# main_v2.net
KiCad netlist of a schematic drawn in EAGLE
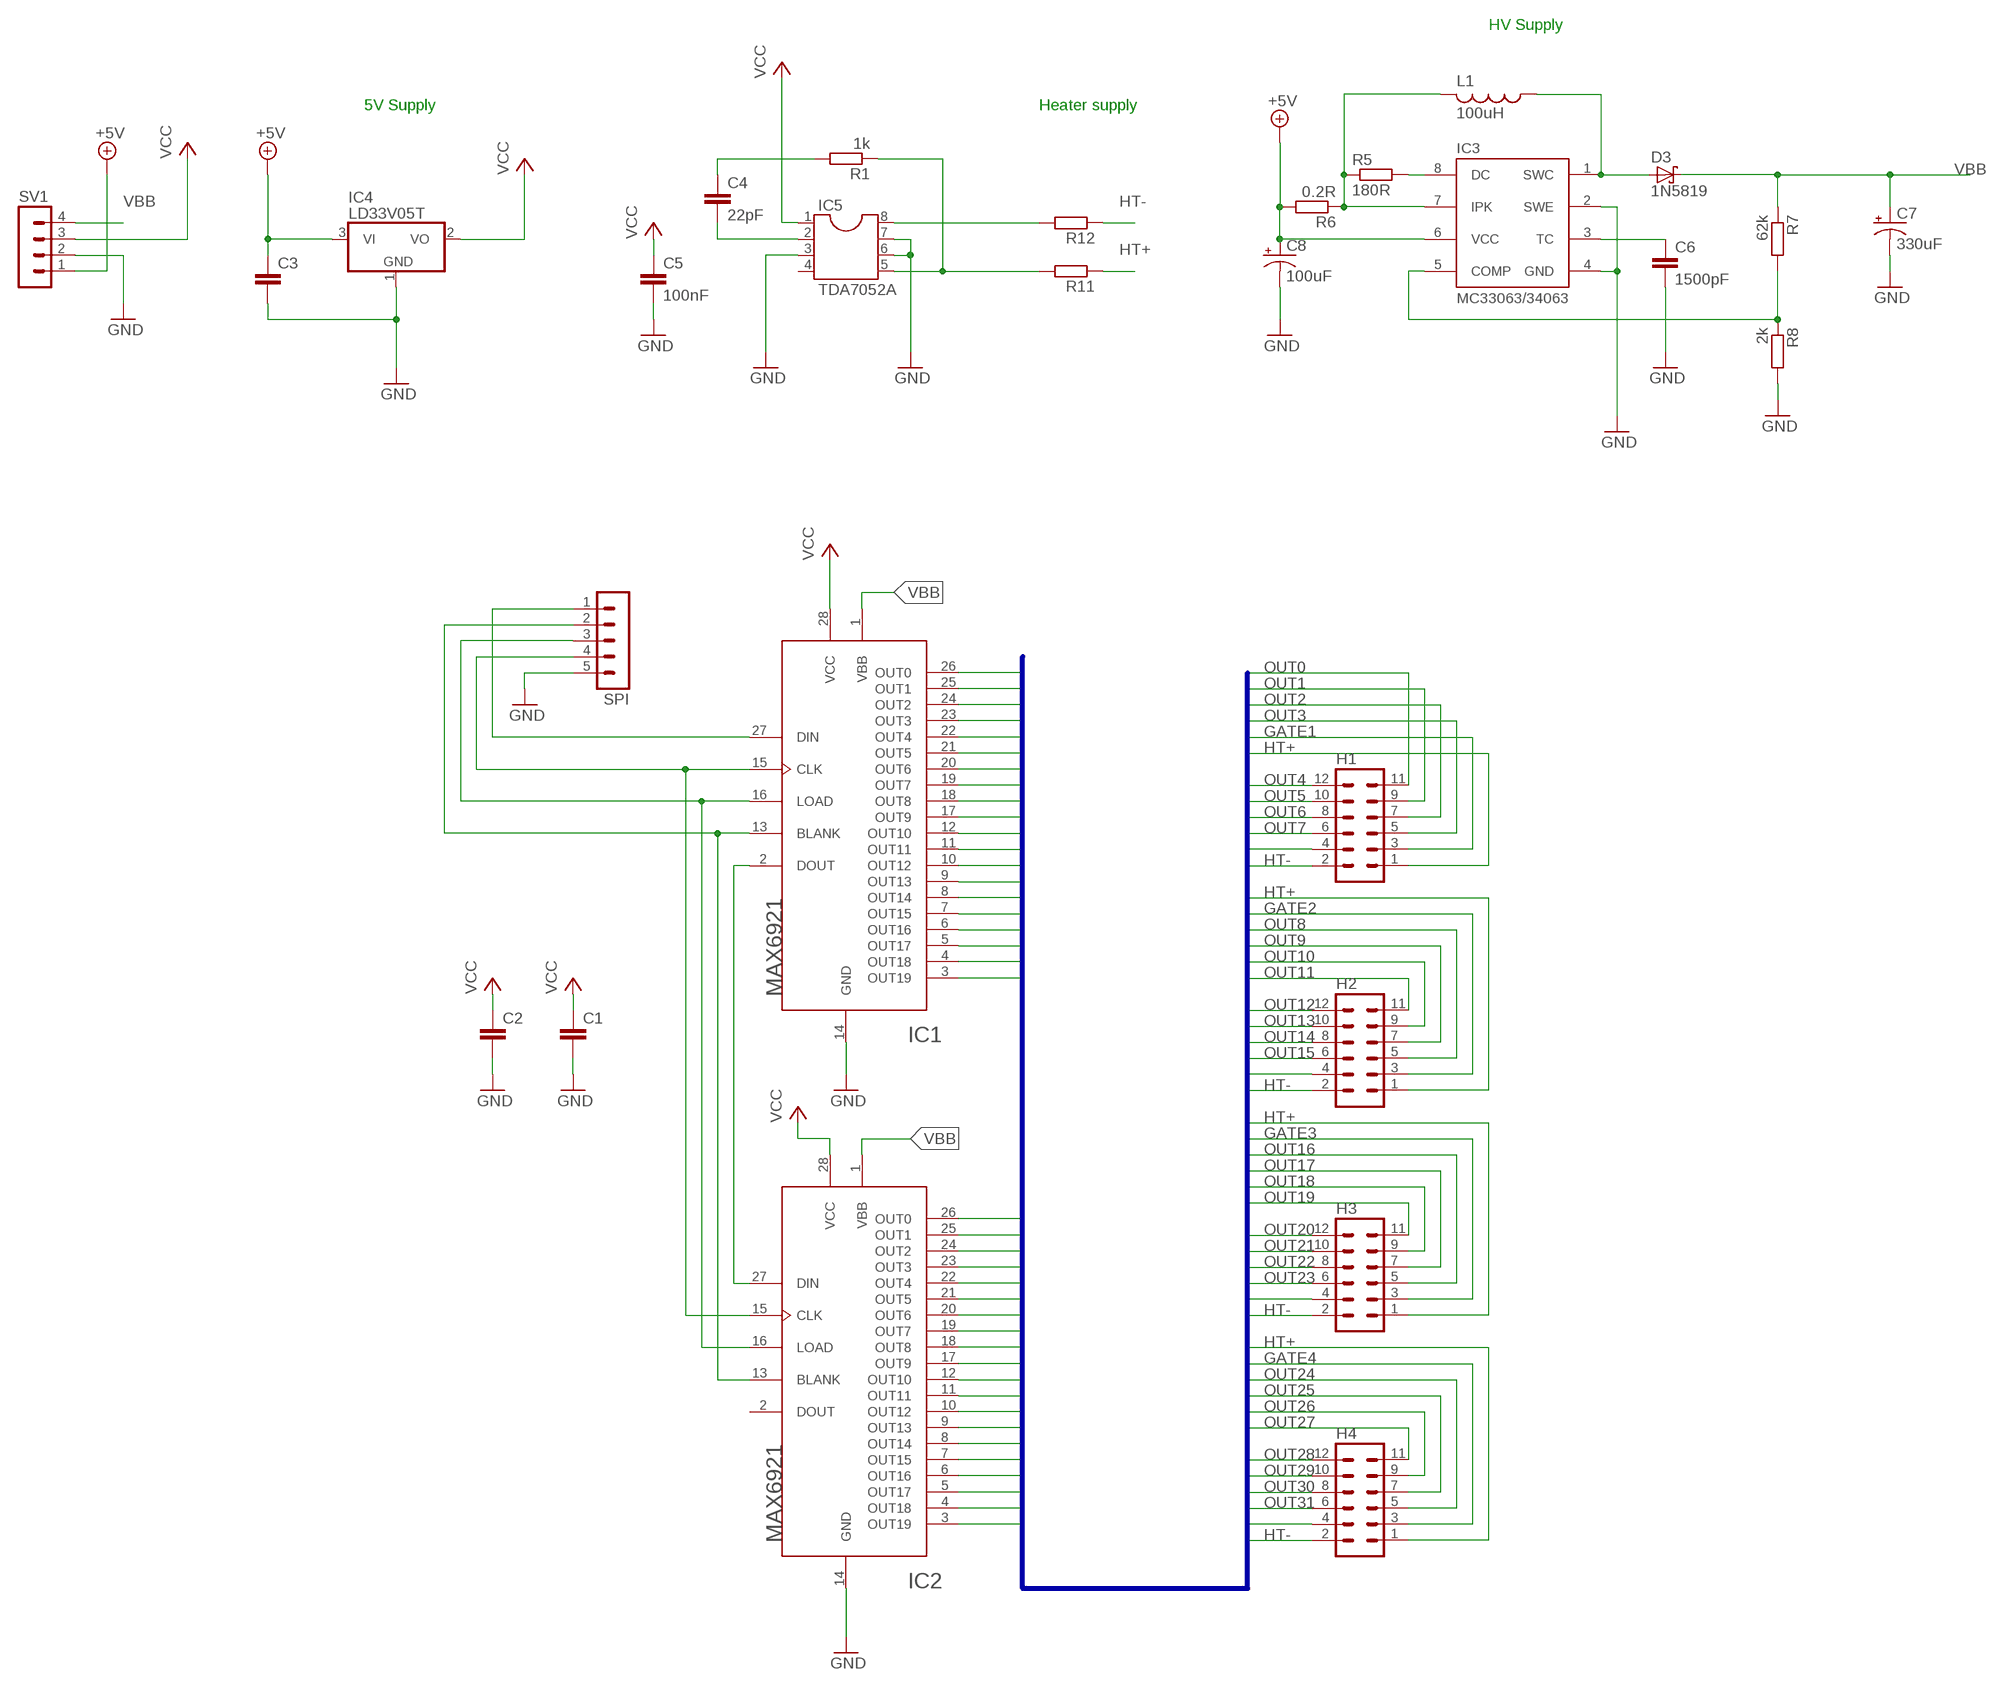
[diagram p0: schematic, sheet 1]

(export (version "E")
  (design (tool "Eeschema 10.0.6"))
  (components
    (comp (ref "C1")
      (value "C-EU025-025X050")
      (footprint "eagle-import:C025-025X050")
      (libsource (lib "eagle-import") (part "C-EU025-025X050"))
    )
    (comp (ref "C2")
      (value "C-EU025-025X050")
      (footprint "eagle-import:C025-025X050")
      (libsource (lib "eagle-import") (part "C-EU025-025X050"))
    )
    (comp (ref "C3")
      (value "C-EU025-025X050")
      (footprint "eagle-import:C025-025X050")
      (libsource (lib "eagle-import") (part "C-EU025-025X050"))
    )
    (comp (ref "C4")
      (value "22pF")
      (footprint "eagle-import:C025-025X050")
      (libsource (lib "eagle-import") (part "C-EU025-025X050"))
    )
    (comp (ref "C5")
      (value "100nF")
      (footprint "eagle-import:C025-025X050")
      (libsource (lib "eagle-import") (part "C-EU025-025X050"))
    )
    (comp (ref "C6")
      (value "1500pF")
      (footprint "eagle-import:C025-025X050")
      (libsource (lib "eagle-import") (part "C-EU025-025X050"))
    )
    (comp (ref "C7")
      (value "330uF")
      (footprint "eagle-import:E3,5-8")
      (libsource (lib "eagle-import") (part "CPOL-USE3.5-8"))
    )
    (comp (ref "C8")
      (value "100uF")
      (footprint "eagle-import:E2,5-5")
      (libsource (lib "eagle-import") (part "CPOL-USE2.5-5"))
    )
    (comp (ref "D3")
      (value "1N5819")
      (footprint "eagle-import:DO35-7")
      (libsource (lib "eagle-import") (part "SCHOTTKY-DIODEDO35-7"))
    )
    (comp (ref "H1")
      (value "MA06-2")
      (footprint "eagle-import:MA06-2")
      (libsource (lib "eagle-import") (part "MA06-2"))
    )
    (comp (ref "H2")
      (value "MA06-2")
      (footprint "eagle-import:MA06-2")
      (libsource (lib "eagle-import") (part "MA06-2"))
    )
    (comp (ref "H3")
      (value "MA06-2")
      (footprint "eagle-import:MA06-2")
      (libsource (lib "eagle-import") (part "MA06-2"))
    )
    (comp (ref "H4")
      (value "MA06-2")
      (footprint "eagle-import:MA06-2")
      (libsource (lib "eagle-import") (part "MA06-2"))
    )
    (comp (ref "IC1")
      (value "MAX6921")
      (footprint "eagle-import:PLCC-S28")
      (libsource (lib "eagle-import") (part "MAX6921"))
    )
    (comp (ref "IC2")
      (value "MAX6921")
      (footprint "eagle-import:PLCC-S28")
      (libsource (lib "eagle-import") (part "MAX6921"))
    )
    (comp (ref "IC3")
      (value "MC33063")
      (footprint "eagle-import:DIL08")
      (libsource (lib "eagle-import") (part "MC33063/MC34063P"))
    )
    (comp (ref "IC4")
      (value "LD33V05T")
      (footprint "eagle-import:TO220H")
      (libsource (lib "eagle-import") (part "LD33VT05"))
    )
    (comp (ref "IC5")
      (value "TDA7052A")
      (footprint "eagle-import:DIL08")
      (libsource (lib "eagle-import") (part "DIL8"))
    )
    (comp (ref "L1")
      (value "100uH")
      (footprint "eagle-import:6000-XXXX-RC")
      (libsource (lib "eagle-import") (part "L-US6000-XXX-RC"))
    )
    (comp (ref "R1")
      (value "1k")
      (footprint "eagle-import:0204_7")
      (libsource (lib "eagle-import") (part "R-EU_0204/7"))
    )
    (comp (ref "R5")
      (value "180R")
      (footprint "eagle-import:0204_7")
      (libsource (lib "eagle-import") (part "R-EU_0204/7"))
    )
    (comp (ref "R6")
      (value "0.2R")
      (footprint "eagle-import:0207_10")
      (libsource (lib "eagle-import") (part "R-EU_0207/10"))
    )
    (comp (ref "R7")
      (value "62k")
      (footprint "eagle-import:0204_7")
      (libsource (lib "eagle-import") (part "R-EU_0204/7"))
    )
    (comp (ref "R8")
      (value "2k")
      (footprint "eagle-import:0204_7")
      (libsource (lib "eagle-import") (part "R-EU_0204/7"))
    )
    (comp (ref "R11")
      (value "R-EU_0204/7")
      (footprint "eagle-import:0204_7")
      (libsource (lib "eagle-import") (part "R-EU_0204/7"))
    )
    (comp (ref "R12")
      (value "R-EU_0204/7")
      (footprint "eagle-import:0204_7")
      (libsource (lib "eagle-import") (part "R-EU_0204/7"))
    )
    (comp (ref "SPI")
      (value "MA05-1")
      (footprint "eagle-import:MA05-1")
      (libsource (lib "eagle-import") (part "MA05-1"))
    )
    (comp (ref "SV1")
      (value "MA04-1")
      (footprint "eagle-import:MA04-1")
      (libsource (lib "eagle-import") (part "MA04-1"))
    )
  )
  (nets
    (net (code "1") (name "+5V") (class "Default")
      (node (ref "C3") (pin "1") (pinfunction "1_1") (pintype "passive"))
      (node (ref "C8") (pin "+") (pinfunction "+_+") (pintype "passive"))
      (node (ref "IC3") (pin "6") (pinfunction "VCC_6") (pintype "power_in"))
      (node (ref "IC4") (pin "3") (pinfunction "VI_3") (pintype "input"))
      (node (ref "R6") (pin "2") (pinfunction "2_2") (pintype "passive"))
      (node (ref "SV1") (pin "1") (pinfunction "1_1") (pintype "passive"))
    )
    (net (code "2") (name "/GATE1") (class "Default")
      (node (ref "H1") (pin "3") (pinfunction "3_3") (pintype "passive"))
      (node (ref "IC2") (pin "12") (pinfunction "OUT10_12") (pintype "output"))
    )
    (net (code "3") (name "/GATE2") (class "Default")
      (node (ref "H2") (pin "3") (pinfunction "3_3") (pintype "passive"))
      (node (ref "IC2") (pin "18") (pinfunction "OUT8_18") (pintype "output"))
    )
    (net (code "4") (name "/GATE3") (class "Default")
      (node (ref "H3") (pin "3") (pinfunction "3_3") (pintype "passive"))
      (node (ref "IC1") (pin "12") (pinfunction "OUT10_12") (pintype "output"))
    )
    (net (code "5") (name "/GATE4") (class "Default")
      (node (ref "H4") (pin "3") (pinfunction "3_3") (pintype "passive"))
      (node (ref "IC1") (pin "25") (pinfunction "OUT1_25") (pintype "output"))
    )
    (net (code "6") (name "/HT+") (class "Default")
      (node (ref "H1") (pin "1") (pinfunction "1_1") (pintype "passive"))
      (node (ref "H2") (pin "1") (pinfunction "1_1") (pintype "passive"))
      (node (ref "H3") (pin "1") (pinfunction "1_1") (pintype "passive"))
      (node (ref "H4") (pin "1") (pinfunction "1_1") (pintype "passive"))
      (node (ref "R11") (pin "1") (pinfunction "1_1") (pintype "passive"))
    )
    (net (code "7") (name "/HT-") (class "Default")
      (node (ref "H1") (pin "2") (pinfunction "2_2") (pintype "passive"))
      (node (ref "H2") (pin "2") (pinfunction "2_2") (pintype "passive"))
      (node (ref "H3") (pin "2") (pinfunction "2_2") (pintype "passive"))
      (node (ref "H4") (pin "2") (pinfunction "2_2") (pintype "passive"))
      (node (ref "R12") (pin "1") (pinfunction "1_1") (pintype "passive"))
    )
    (net (code "8") (name "/OUT0") (class "Default")
      (node (ref "H1") (pin "11") (pinfunction "11_11") (pintype "passive"))
      (node (ref "IC2") (pin "10") (pinfunction "OUT12_10") (pintype "output"))
    )
    (net (code "9") (name "/OUT1") (class "Default")
      (node (ref "H1") (pin "9") (pinfunction "9_9") (pintype "passive"))
      (node (ref "IC2") (pin "7") (pinfunction "OUT15_7") (pintype "output"))
    )
    (net (code "10") (name "/OUT2") (class "Default")
      (node (ref "H1") (pin "7") (pinfunction "7_7") (pintype "passive"))
      (node (ref "IC2") (pin "5") (pinfunction "OUT17_5") (pintype "output"))
    )
    (net (code "11") (name "/OUT3") (class "Default")
      (node (ref "H1") (pin "5") (pinfunction "5_5") (pintype "passive"))
      (node (ref "IC2") (pin "11") (pinfunction "OUT11_11") (pintype "output"))
    )
    (net (code "12") (name "/OUT4") (class "Default")
      (node (ref "H1") (pin "12") (pinfunction "12_12") (pintype "passive"))
      (node (ref "IC2") (pin "9") (pinfunction "OUT13_9") (pintype "output"))
    )
    (net (code "13") (name "/OUT5") (class "Default")
      (node (ref "H1") (pin "10") (pinfunction "10_10") (pintype "passive"))
      (node (ref "IC2") (pin "8") (pinfunction "OUT14_8") (pintype "output"))
    )
    (net (code "14") (name "/OUT6") (class "Default")
      (node (ref "H1") (pin "8") (pinfunction "8_8") (pintype "passive"))
      (node (ref "IC2") (pin "6") (pinfunction "OUT16_6") (pintype "output"))
    )
    (net (code "15") (name "/OUT7") (class "Default")
      (node (ref "H1") (pin "6") (pinfunction "6_6") (pintype "passive"))
      (node (ref "IC2") (pin "3") (pinfunction "OUT19_3") (pintype "output"))
    )
    (net (code "16") (name "/OUT8") (class "Default")
      (node (ref "H2") (pin "5") (pinfunction "5_5") (pintype "passive"))
      (node (ref "IC2") (pin "21") (pinfunction "OUT5_21") (pintype "output"))
    )
    (net (code "17") (name "/OUT9") (class "Default")
      (node (ref "H2") (pin "7") (pinfunction "7_7") (pintype "passive"))
      (node (ref "IC2") (pin "23") (pinfunction "OUT3_23") (pintype "output"))
    )
    (net (code "18") (name "/OUT10") (class "Default")
      (node (ref "H2") (pin "9") (pinfunction "9_9") (pintype "passive"))
      (node (ref "IC2") (pin "25") (pinfunction "OUT1_25") (pintype "output"))
    )
    (net (code "19") (name "/OUT11") (class "Default")
      (node (ref "H2") (pin "11") (pinfunction "11_11") (pintype "passive"))
      (node (ref "IC2") (pin "19") (pinfunction "OUT7_19") (pintype "output"))
    )
    (net (code "20") (name "/OUT12") (class "Default")
      (node (ref "H2") (pin "12") (pinfunction "12_12") (pintype "passive"))
      (node (ref "IC2") (pin "20") (pinfunction "OUT6_20") (pintype "output"))
    )
    (net (code "21") (name "/OUT13") (class "Default")
      (node (ref "H2") (pin "10") (pinfunction "10_10") (pintype "passive"))
      (node (ref "IC2") (pin "26") (pinfunction "OUT0_26") (pintype "output"))
    )
    (net (code "22") (name "/OUT14") (class "Default")
      (node (ref "H2") (pin "8") (pinfunction "8_8") (pintype "passive"))
      (node (ref "IC2") (pin "24") (pinfunction "OUT2_24") (pintype "output"))
    )
    (net (code "23") (name "/OUT15") (class "Default")
      (node (ref "H2") (pin "6") (pinfunction "6_6") (pintype "passive"))
      (node (ref "IC2") (pin "22") (pinfunction "OUT4_22") (pintype "output"))
    )
    (net (code "24") (name "/OUT16") (class "Default")
      (node (ref "H3") (pin "5") (pinfunction "5_5") (pintype "passive"))
      (node (ref "IC1") (pin "11") (pinfunction "OUT11_11") (pintype "output"))
    )
    (net (code "25") (name "/OUT17") (class "Default")
      (node (ref "H3") (pin "7") (pinfunction "7_7") (pintype "passive"))
      (node (ref "IC1") (pin "8") (pinfunction "OUT14_8") (pintype "output"))
    )
    (net (code "26") (name "/OUT18") (class "Default")
      (node (ref "H3") (pin "9") (pinfunction "9_9") (pintype "passive"))
      (node (ref "IC1") (pin "9") (pinfunction "OUT13_9") (pintype "output"))
    )
    (net (code "27") (name "/OUT19") (class "Default")
      (node (ref "H3") (pin "11") (pinfunction "11_11") (pintype "passive"))
      (node (ref "IC1") (pin "10") (pinfunction "OUT12_10") (pintype "output"))
    )
    (net (code "28") (name "/OUT20") (class "Default")
      (node (ref "H3") (pin "12") (pinfunction "12_12") (pintype "passive"))
      (node (ref "IC1") (pin "7") (pinfunction "OUT15_7") (pintype "output"))
    )
    (net (code "29") (name "/OUT21") (class "Default")
      (node (ref "H3") (pin "10") (pinfunction "10_10") (pintype "passive"))
      (node (ref "IC1") (pin "6") (pinfunction "OUT16_6") (pintype "output"))
    )
    (net (code "30") (name "/OUT22") (class "Default")
      (node (ref "H3") (pin "8") (pinfunction "8_8") (pintype "passive"))
      (node (ref "IC1") (pin "5") (pinfunction "OUT17_5") (pintype "output"))
    )
    (net (code "31") (name "/OUT23") (class "Default")
      (node (ref "H3") (pin "6") (pinfunction "6_6") (pintype "passive"))
      (node (ref "IC1") (pin "3") (pinfunction "OUT19_3") (pintype "output"))
    )
    (net (code "32") (name "/OUT24") (class "Default")
      (node (ref "H4") (pin "5") (pinfunction "5_5") (pintype "passive"))
      (node (ref "IC1") (pin "23") (pinfunction "OUT3_23") (pintype "output"))
    )
    (net (code "33") (name "/OUT25") (class "Default")
      (node (ref "H4") (pin "7") (pinfunction "7_7") (pintype "passive"))
      (node (ref "IC1") (pin "21") (pinfunction "OUT5_21") (pintype "output"))
    )
    (net (code "34") (name "/OUT26") (class "Default")
      (node (ref "H4") (pin "9") (pinfunction "9_9") (pintype "passive"))
      (node (ref "IC1") (pin "22") (pinfunction "OUT4_22") (pintype "output"))
    )
    (net (code "35") (name "/OUT27") (class "Default")
      (node (ref "H4") (pin "11") (pinfunction "11_11") (pintype "passive"))
      (node (ref "IC1") (pin "19") (pinfunction "OUT7_19") (pintype "output"))
    )
    (net (code "36") (name "/OUT28") (class "Default")
      (node (ref "H4") (pin "12") (pinfunction "12_12") (pintype "passive"))
      (node (ref "IC1") (pin "20") (pinfunction "OUT6_20") (pintype "output"))
    )
    (net (code "37") (name "/OUT29") (class "Default")
      (node (ref "H4") (pin "10") (pinfunction "10_10") (pintype "passive"))
      (node (ref "IC1") (pin "18") (pinfunction "OUT8_18") (pintype "output"))
    )
    (net (code "38") (name "/OUT30") (class "Default")
      (node (ref "H4") (pin "8") (pinfunction "8_8") (pintype "passive"))
      (node (ref "IC1") (pin "17") (pinfunction "OUT9_17") (pintype "output"))
    )
    (net (code "39") (name "/OUT31") (class "Default")
      (node (ref "H4") (pin "6") (pinfunction "6_6") (pintype "passive"))
      (node (ref "IC1") (pin "24") (pinfunction "OUT2_24") (pintype "output"))
    )
    (net (code "40") (name "/SPARE1") (class "Default")
      (node (ref "H1") (pin "4") (pinfunction "4_4") (pintype "passive"))
      (node (ref "IC2") (pin "4") (pinfunction "OUT18_4") (pintype "output"))
    )
    (net (code "41") (name "/SPARE2") (class "Default")
      (node (ref "H2") (pin "4") (pinfunction "4_4") (pintype "passive"))
      (node (ref "IC2") (pin "17") (pinfunction "OUT9_17") (pintype "output"))
    )
    (net (code "42") (name "/SPARE3") (class "Default")
      (node (ref "H3") (pin "4") (pinfunction "4_4") (pintype "passive"))
      (node (ref "IC1") (pin "4") (pinfunction "OUT18_4") (pintype "output"))
    )
    (net (code "43") (name "/SPARE4") (class "Default")
      (node (ref "H4") (pin "4") (pinfunction "4_4") (pintype "passive"))
      (node (ref "IC1") (pin "26") (pinfunction "OUT0_26") (pintype "output"))
    )
    (net (code "44") (name "GND") (class "Default")
      (node (ref "C1") (pin "2") (pinfunction "2_2") (pintype "passive"))
      (node (ref "C2") (pin "2") (pinfunction "2_2") (pintype "passive"))
      (node (ref "C3") (pin "2") (pinfunction "2_2") (pintype "passive"))
      (node (ref "C5") (pin "2") (pinfunction "2_2") (pintype "passive"))
      (node (ref "C6") (pin "2") (pinfunction "2_2") (pintype "passive"))
      (node (ref "C7") (pin "-") (pinfunction "-_-") (pintype "passive"))
      (node (ref "C8") (pin "-") (pinfunction "-_-") (pintype "passive"))
      (node (ref "IC1") (pin "14") (pinfunction "GND_14") (pintype "power_in"))
      (node (ref "IC2") (pin "14") (pinfunction "GND_14") (pintype "power_in"))
      (node (ref "IC3") (pin "2") (pinfunction "SWE_2") (pintype "input"))
      (node (ref "IC3") (pin "4") (pinfunction "GND_4") (pintype "power_in"))
      (node (ref "IC4") (pin "1") (pinfunction "GND_1") (pintype "passive"))
      (node (ref "IC5") (pin "3") (pinfunction "3_3") (pintype "passive"))
      (node (ref "IC5") (pin "6") (pinfunction "6_6") (pintype "passive"))
      (node (ref "IC5") (pin "7") (pinfunction "7_7") (pintype "passive"))
      (node (ref "R8") (pin "2") (pinfunction "2_2") (pintype "passive"))
      (node (ref "SPI") (pin "5") (pinfunction "5_5") (pintype "passive"))
      (node (ref "SV1") (pin "2") (pinfunction "2_2") (pintype "passive"))
    )
    (net (code "45") (name "Net-(C4-Pad1)") (class "Default")
      (node (ref "C4") (pin "1") (pinfunction "1_1") (pintype "passive"))
      (node (ref "R1") (pin "2") (pinfunction "2_2") (pintype "passive"))
    )
    (net (code "46") (name "Net-(C4-Pad2)") (class "Default")
      (node (ref "C4") (pin "2") (pinfunction "2_2") (pintype "passive"))
      (node (ref "IC5") (pin "2") (pinfunction "2_2") (pintype "passive"))
    )
    (net (code "47") (name "Net-(IC1-BLANK)") (class "Default")
      (node (ref "IC1") (pin "13") (pinfunction "BLANK_13") (pintype "input"))
      (node (ref "IC2") (pin "13") (pinfunction "BLANK_13") (pintype "input"))
      (node (ref "SPI") (pin "2") (pinfunction "2_2") (pintype "passive"))
    )
    (net (code "48") (name "Net-(IC1-CLK)") (class "Default")
      (node (ref "IC1") (pin "15") (pinfunction "CLK_15") (pintype "input"))
      (node (ref "IC2") (pin "15") (pinfunction "CLK_15") (pintype "input"))
      (node (ref "SPI") (pin "4") (pinfunction "4_4") (pintype "passive"))
    )
    (net (code "49") (name "Net-(IC1-DIN)") (class "Default")
      (node (ref "IC1") (pin "27") (pinfunction "DIN_27") (pintype "input"))
      (node (ref "SPI") (pin "1") (pinfunction "1_1") (pintype "passive"))
    )
    (net (code "50") (name "Net-(IC1-DOUT)") (class "Default")
      (node (ref "IC1") (pin "2") (pinfunction "DOUT_2") (pintype "output"))
      (node (ref "IC2") (pin "27") (pinfunction "DIN_27") (pintype "input"))
    )
    (net (code "51") (name "Net-(IC1-LOAD)") (class "Default")
      (node (ref "IC1") (pin "16") (pinfunction "LOAD_16") (pintype "input"))
      (node (ref "IC2") (pin "16") (pinfunction "LOAD_16") (pintype "input"))
      (node (ref "SPI") (pin "3") (pinfunction "3_3") (pintype "passive"))
    )
    (net (code "52") (name "Net-(IC3-COMP)") (class "Default")
      (node (ref "IC3") (pin "5") (pinfunction "COMP_5") (pintype "input"))
      (node (ref "R7") (pin "2") (pinfunction "2_2") (pintype "passive"))
      (node (ref "R8") (pin "1") (pinfunction "1_1") (pintype "passive"))
    )
    (net (code "53") (name "Net-(IC3-DC)") (class "Default")
      (node (ref "IC3") (pin "8") (pinfunction "DC_8") (pintype "input"))
      (node (ref "R5") (pin "2") (pinfunction "2_2") (pintype "passive"))
    )
    (net (code "54") (name "Net-(IC3-IPK)") (class "Default")
      (node (ref "IC3") (pin "7") (pinfunction "IPK_7") (pintype "bidirectional"))
      (node (ref "L1") (pin "2") (pinfunction "2_2") (pintype "passive"))
      (node (ref "R5") (pin "1") (pinfunction "1_1") (pintype "passive"))
      (node (ref "R6") (pin "1") (pinfunction "1_1") (pintype "passive"))
    )
    (net (code "55") (name "Net-(IC3-SWC)") (class "Default")
      (node (ref "D3") (pin "A") (pinfunction "A_A") (pintype "passive"))
      (node (ref "IC3") (pin "1") (pinfunction "SWC_1") (pintype "input"))
      (node (ref "L1") (pin "1") (pinfunction "1_1") (pintype "passive"))
    )
    (net (code "56") (name "Net-(IC3-TC)") (class "Default")
      (node (ref "C6") (pin "1") (pinfunction "1_1") (pintype "passive"))
      (node (ref "IC3") (pin "3") (pinfunction "TC_3") (pintype "input"))
    )
    (net (code "57") (name "Net-(IC5-Pad5)") (class "Default")
      (node (ref "IC5") (pin "5") (pinfunction "5_5") (pintype "passive"))
      (node (ref "R1") (pin "1") (pinfunction "1_1") (pintype "passive"))
      (node (ref "R11") (pin "2") (pinfunction "2_2") (pintype "passive"))
    )
    (net (code "58") (name "Net-(IC5-Pad8)") (class "Default")
      (node (ref "IC5") (pin "8") (pinfunction "8_8") (pintype "passive"))
      (node (ref "R12") (pin "2") (pinfunction "2_2") (pintype "passive"))
    )
    (net (code "59") (name "VBB") (class "Default")
      (node (ref "C7") (pin "+") (pinfunction "+_+") (pintype "passive"))
      (node (ref "D3") (pin "C") (pinfunction "C_C") (pintype "passive"))
      (node (ref "IC1") (pin "1") (pinfunction "VBB_1") (pintype "power_in"))
      (node (ref "IC2") (pin "1") (pinfunction "VBB_1") (pintype "power_in"))
      (node (ref "R7") (pin "1") (pinfunction "1_1") (pintype "passive"))
      (node (ref "SV1") (pin "4") (pinfunction "4_4") (pintype "passive"))
    )
    (net (code "60") (name "VCC") (class "Default")
      (node (ref "C1") (pin "1") (pinfunction "1_1") (pintype "passive"))
      (node (ref "C2") (pin "1") (pinfunction "1_1") (pintype "passive"))
      (node (ref "C5") (pin "1") (pinfunction "1_1") (pintype "passive"))
      (node (ref "IC1") (pin "28") (pinfunction "VCC_28") (pintype "power_in"))
      (node (ref "IC2") (pin "28") (pinfunction "VCC_28") (pintype "power_in"))
      (node (ref "IC4") (pin "2") (pinfunction "VO_2") (pintype "passive"))
      (node (ref "IC5") (pin "1") (pinfunction "1_1") (pintype "passive"))
      (node (ref "SV1") (pin "3") (pinfunction "3_3") (pintype "passive"))
    )
    (net (code "61") (name "unconnected-(IC2-DOUT-Pad2)") (class "Default")
      (node (ref "IC2") (pin "2") (pinfunction "DOUT_2") (pintype "output"))
    )
    (net (code "62") (name "unconnected-(IC5-Pad4)") (class "Default")
      (node (ref "IC5") (pin "4") (pinfunction "4_4") (pintype "passive"))
    )
  )
)
